# Sheet1.net
KiCad netlist of a schematic drawn in Altium Designer
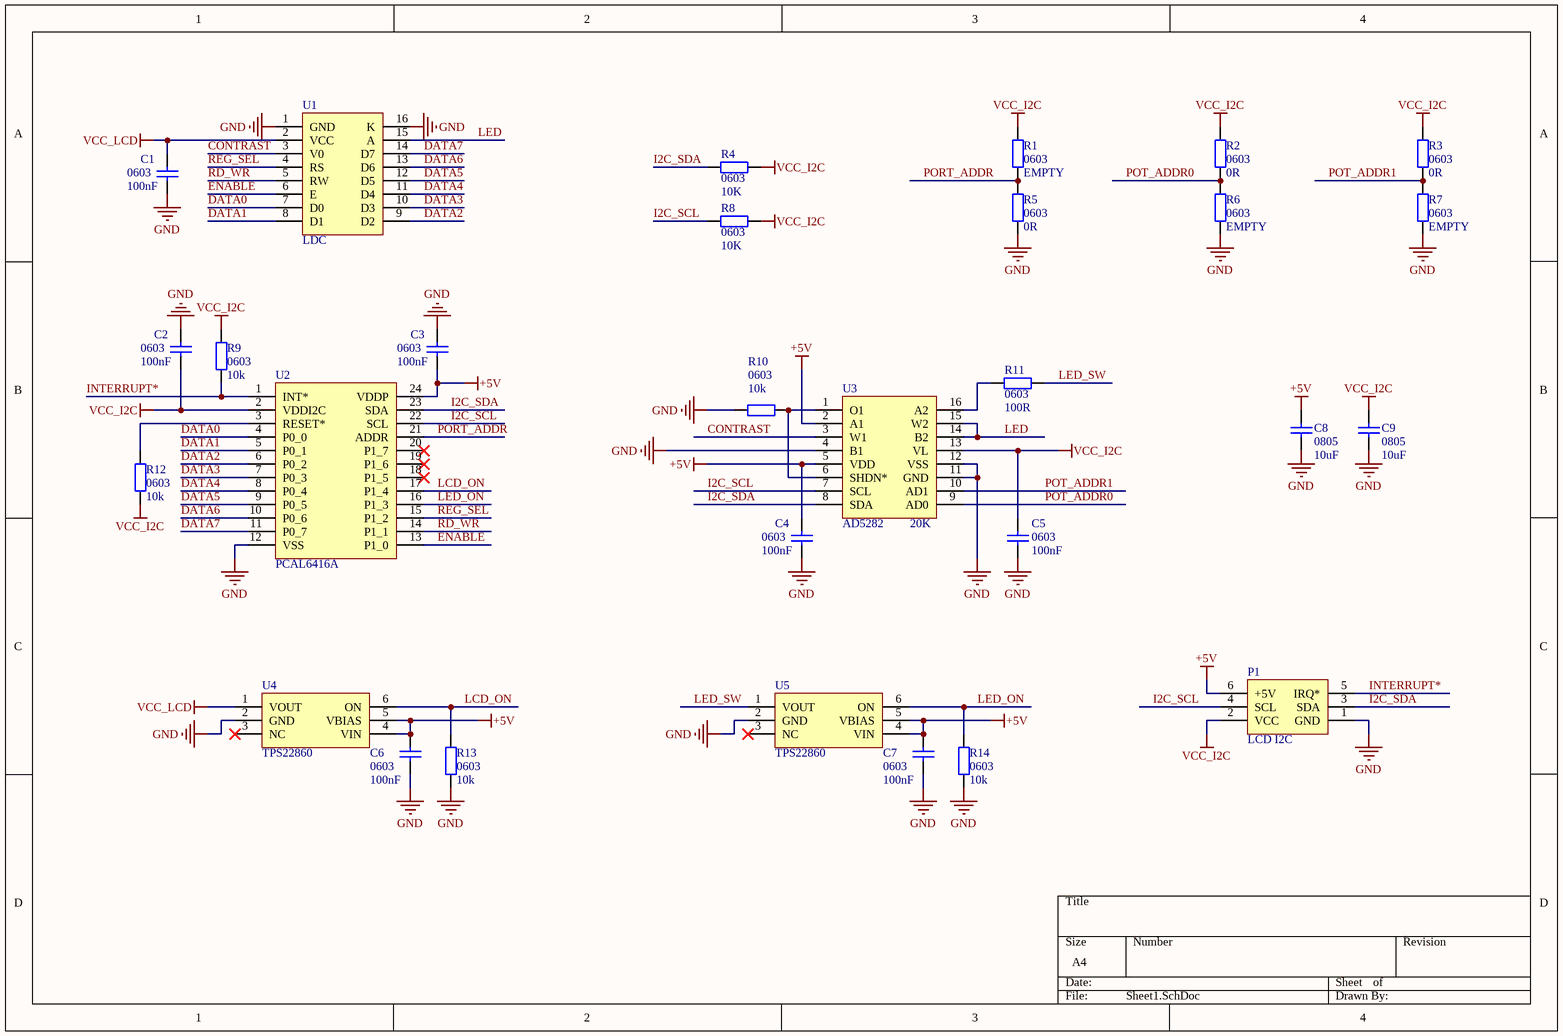
[diagram p0: Sheet1.SchDoc]

(export (version "E")
  (design (tool "Eeschema 10.0.6"))
  (components
    (comp (ref "C1")
      (value "0603")
      (footprint "0603_HandSoldering")
      (description "Capacitor")
      (fields (field (name "ALTIUM_VALUE") "100nF"))
      (libsource (lib "Schlib") (part "Capacitor"))
    )
    (comp (ref "C2")
      (value "0603")
      (footprint "0603_HandSoldering")
      (description "Capacitor")
      (fields (field (name "ALTIUM_VALUE") "100nF"))
      (libsource (lib "Schlib") (part "Capacitor"))
    )
    (comp (ref "C3")
      (value "0603")
      (footprint "0603_HandSoldering")
      (description "Capacitor")
      (fields (field (name "ALTIUM_VALUE") "100nF"))
      (libsource (lib "Schlib") (part "Capacitor"))
    )
    (comp (ref "C4")
      (value "0603")
      (footprint "0603_HandSoldering")
      (description "Capacitor")
      (fields (field (name "ALTIUM_VALUE") "100nF"))
      (libsource (lib "Schlib") (part "Capacitor"))
    )
    (comp (ref "C5")
      (value "0603")
      (footprint "0603_HandSoldering")
      (description "Capacitor")
      (fields (field (name "ALTIUM_VALUE") "100nF"))
      (libsource (lib "Schlib") (part "Capacitor"))
    )
    (comp (ref "C6")
      (value "0603")
      (footprint "0603_HandSoldering")
      (description "Capacitor")
      (fields (field (name "ALTIUM_VALUE") "100nF"))
      (libsource (lib "Schlib") (part "Capacitor"))
    )
    (comp (ref "C7")
      (value "0603")
      (footprint "0603_HandSoldering")
      (description "Capacitor")
      (fields (field (name "ALTIUM_VALUE") "100nF"))
      (libsource (lib "Schlib") (part "Capacitor"))
    )
    (comp (ref "C8")
      (value "0805")
      (footprint "0805")
      (description "Capacitor")
      (fields (field (name "ALTIUM_VALUE") "10uF"))
      (libsource (lib "Schlib") (part "Capacitor"))
    )
    (comp (ref "C9")
      (value "0805")
      (footprint "0805")
      (description "Capacitor")
      (fields (field (name "ALTIUM_VALUE") "10uF"))
      (libsource (lib "Schlib") (part "Capacitor"))
    )
    (comp (ref "P1")
      (value "LCD I2C")
      (footprint "IDC6")
      (description "LCD I2C interface")
      (libsource (lib "Schlib") (part "LCD_I2C"))
    )
    (comp (ref "R1")
      (value "0603")
      (footprint "0603_HandSoldering")
      (description "Resistor")
      (fields (field (name "ALTIUM_VALUE") "EMPTY"))
      (libsource (lib "Schlib") (part "Resistor"))
    )
    (comp (ref "R2")
      (value "0603")
      (footprint "0603_HandSoldering")
      (description "Resistor")
      (fields (field (name "ALTIUM_VALUE") "0R"))
      (libsource (lib "Schlib") (part "Resistor"))
    )
    (comp (ref "R3")
      (value "0603")
      (footprint "0603_HandSoldering")
      (description "Resistor")
      (fields (field (name "ALTIUM_VALUE") "0R"))
      (libsource (lib "Schlib") (part "Resistor"))
    )
    (comp (ref "R4")
      (value "0603")
      (footprint "0603_HandSoldering")
      (description "Resistor")
      (fields (field (name "ALTIUM_VALUE") "10K"))
      (libsource (lib "") (part "Resistor_1"))
    )
    (comp (ref "R5")
      (value "0603")
      (footprint "0603_HandSoldering")
      (description "Resistor")
      (fields (field (name "ALTIUM_VALUE") "0R"))
      (libsource (lib "Schlib") (part "Resistor"))
    )
    (comp (ref "R6")
      (value "0603")
      (footprint "0603_HandSoldering")
      (description "Resistor")
      (fields (field (name "ALTIUM_VALUE") "EMPTY"))
      (libsource (lib "Schlib") (part "Resistor"))
    )
    (comp (ref "R7")
      (value "0603")
      (footprint "0603_HandSoldering")
      (description "Resistor")
      (fields (field (name "ALTIUM_VALUE") "EMPTY"))
      (libsource (lib "Schlib") (part "Resistor"))
    )
    (comp (ref "R8")
      (value "0603")
      (footprint "0603_HandSoldering")
      (description "Resistor")
      (fields (field (name "ALTIUM_VALUE") "10K"))
      (libsource (lib "") (part "Resistor_1"))
    )
    (comp (ref "R9")
      (value "0603")
      (footprint "0603_HandSoldering")
      (description "Resistor")
      (fields (field (name "ALTIUM_VALUE") "10k"))
      (libsource (lib "") (part "Resistor_3"))
    )
    (comp (ref "R10")
      (value "0603")
      (footprint "0603_HandSoldering")
      (description "Resistor")
      (fields (field (name "ALTIUM_VALUE") "10k"))
      (libsource (lib "") (part "Resistor_1"))
    )
    (comp (ref "R11")
      (value "0603")
      (footprint "0603_HandSoldering")
      (description "Resistor")
      (fields (field (name "ALTIUM_VALUE") "100R"))
      (libsource (lib "") (part "Resistor_2"))
    )
    (comp (ref "R12")
      (value "0603")
      (footprint "0603_HandSoldering")
      (description "Resistor")
      (fields (field (name "ALTIUM_VALUE") "10k"))
      (libsource (lib "") (part "Resistor_3"))
    )
    (comp (ref "R13")
      (value "0603")
      (footprint "0603_HandSoldering")
      (description "Resistor")
      (fields (field (name "ALTIUM_VALUE") "10k"))
      (libsource (lib "Schlib") (part "Resistor"))
    )
    (comp (ref "R14")
      (value "0603")
      (footprint "0603_HandSoldering")
      (description "Resistor")
      (fields (field (name "ALTIUM_VALUE") "10k"))
      (libsource (lib "Schlib") (part "Resistor"))
    )
    (comp (ref "U1")
      (value "LDC")
      (footprint "LCD_2x16_Board")
      (description "2x16 LCD PCB")
      (libsource (lib "Schlib") (part "LCD_2x16_Board"))
    )
    (comp (ref "U2")
      (value "PCAL6416A")
      (footprint "PCAL6416A_TSOP24")
      (description "I2C to parallel converter")
      (libsource (lib "Schlib") (part "PCAL6416A"))
    )
    (comp (ref "U3")
      (value "AD5282")
      (footprint "AD5282_TSSOP16")
      (description "Dual digital potentiometer")
      (fields (field (name "ALTIUM_VALUE") "20K"))
      (libsource (lib "Schlib") (part "AD5282"))
    )
    (comp (ref "U4")
      (value "TPS22860")
      (footprint "TPS22860_SOT23_6")
      (description "Power switch")
      (libsource (lib "Schlib") (part "TPS22860"))
    )
    (comp (ref "U5")
      (value "TPS22860")
      (footprint "TPS22860_SOT23_6")
      (description "Power switch")
      (libsource (lib "Schlib") (part "TPS22860"))
    )
  )
  (nets
    (net (code "1") (name "+5V") (class "Default")
      (node (ref "C3") (pin "1") (pinfunction "1_1") (pintype "passive"))
      (node (ref "C4") (pin "2") (pinfunction "2_2") (pintype "passive"))
      (node (ref "C6") (pin "1") (pinfunction "1_1") (pintype "passive"))
      (node (ref "C7") (pin "1") (pinfunction "1_1") (pintype "passive"))
      (node (ref "C8") (pin "2") (pinfunction "2_2") (pintype "passive"))
      (node (ref "P1") (pin "6") (pinfunction "+5V_6") (pintype "passive"))
      (node (ref "U2") (pin "24") (pinfunction "VDDP_24") (pintype "passive"))
      (node (ref "U3") (pin "2") (pinfunction "A1_2") (pintype "passive"))
      (node (ref "U3") (pin "5") (pinfunction "VDD_5") (pintype "passive"))
      (node (ref "U4") (pin "4") (pinfunction "VIN_4") (pintype "passive"))
      (node (ref "U4") (pin "5") (pinfunction "VBIAS_5") (pintype "passive"))
      (node (ref "U5") (pin "4") (pinfunction "VIN_4") (pintype "passive"))
      (node (ref "U5") (pin "5") (pinfunction "VBIAS_5") (pintype "passive"))
    )
    (net (code "2") (name "/CONTRAST") (class "Default")
      (node (ref "U1") (pin "3") (pinfunction "V0_3") (pintype "passive"))
      (node (ref "U3") (pin "3") (pinfunction "W1_3") (pintype "passive"))
    )
    (net (code "3") (name "/DATA0") (class "Default")
      (node (ref "U1") (pin "7") (pinfunction "D0_7") (pintype "passive"))
      (node (ref "U2") (pin "4") (pinfunction "P0_0_4") (pintype "passive"))
    )
    (net (code "4") (name "/DATA1") (class "Default")
      (node (ref "U1") (pin "8") (pinfunction "D1_8") (pintype "passive"))
      (node (ref "U2") (pin "5") (pinfunction "P0_1_5") (pintype "passive"))
    )
    (net (code "5") (name "/DATA2") (class "Default")
      (node (ref "U1") (pin "9") (pinfunction "D2_9") (pintype "passive"))
      (node (ref "U2") (pin "6") (pinfunction "P0_2_6") (pintype "passive"))
    )
    (net (code "6") (name "/DATA3") (class "Default")
      (node (ref "U1") (pin "10") (pinfunction "D3_10") (pintype "passive"))
      (node (ref "U2") (pin "7") (pinfunction "P0_3_7") (pintype "passive"))
    )
    (net (code "7") (name "/DATA4") (class "Default")
      (node (ref "U1") (pin "11") (pinfunction "D4_11") (pintype "passive"))
      (node (ref "U2") (pin "8") (pinfunction "P0_4_8") (pintype "passive"))
    )
    (net (code "8") (name "/DATA5") (class "Default")
      (node (ref "U1") (pin "12") (pinfunction "D5_12") (pintype "passive"))
      (node (ref "U2") (pin "9") (pinfunction "P0_5_9") (pintype "passive"))
    )
    (net (code "9") (name "/DATA6") (class "Default")
      (node (ref "U1") (pin "13") (pinfunction "D6_13") (pintype "passive"))
      (node (ref "U2") (pin "10") (pinfunction "P0_6_10") (pintype "passive"))
    )
    (net (code "10") (name "/DATA7") (class "Default")
      (node (ref "U1") (pin "14") (pinfunction "D7_14") (pintype "passive"))
      (node (ref "U2") (pin "11") (pinfunction "P0_7_11") (pintype "passive"))
    )
    (net (code "11") (name "/ENABLE") (class "Default")
      (node (ref "U1") (pin "6") (pinfunction "E_6") (pintype "passive"))
      (node (ref "U2") (pin "13") (pinfunction "P1_0_13") (pintype "passive"))
    )
    (net (code "12") (name "/I2C_SCL") (class "Default")
      (node (ref "P1") (pin "4") (pinfunction "SCL_4") (pintype "passive"))
      (node (ref "R8") (pin "1") (pinfunction "1_1") (pintype "passive"))
      (node (ref "U2") (pin "22") (pinfunction "SCL_22") (pintype "passive"))
      (node (ref "U3") (pin "7") (pinfunction "SCL_7") (pintype "passive"))
    )
    (net (code "13") (name "/I2C_SDA") (class "Default")
      (node (ref "P1") (pin "3") (pinfunction "SDA_3") (pintype "passive"))
      (node (ref "R4") (pin "1") (pinfunction "1_1") (pintype "passive"))
      (node (ref "U2") (pin "23") (pinfunction "SDA_23") (pintype "passive"))
      (node (ref "U3") (pin "8") (pinfunction "SDA_8") (pintype "passive"))
    )
    (net (code "14") (name "/INTERRUPT*") (class "Default")
      (node (ref "P1") (pin "5") (pinfunction "IRQ*_5") (pintype "passive"))
      (node (ref "R9") (pin "2") (pinfunction "2_2") (pintype "passive"))
      (node (ref "U2") (pin "1") (pinfunction "INT*_1") (pintype "passive"))
    )
    (net (code "15") (name "/LCD_ON") (class "Default")
      (node (ref "R13") (pin "2") (pinfunction "2_2") (pintype "passive"))
      (node (ref "U2") (pin "17") (pinfunction "P1_4_17") (pintype "passive"))
      (node (ref "U4") (pin "6") (pinfunction "ON_6") (pintype "passive"))
    )
    (net (code "16") (name "/LED") (class "Default")
      (node (ref "U1") (pin "15") (pinfunction "A_15") (pintype "passive"))
      (node (ref "U3") (pin "14") (pinfunction "B2_14") (pintype "passive"))
      (node (ref "U3") (pin "15") (pinfunction "W2_15") (pintype "passive"))
    )
    (net (code "17") (name "/LED_ON") (class "Default")
      (node (ref "R14") (pin "2") (pinfunction "2_2") (pintype "passive"))
      (node (ref "U2") (pin "16") (pinfunction "P1_3_16") (pintype "passive"))
      (node (ref "U5") (pin "6") (pinfunction "ON_6") (pintype "passive"))
    )
    (net (code "18") (name "/LED_SW") (class "Default")
      (node (ref "R11") (pin "1") (pinfunction "1_1") (pintype "passive"))
      (node (ref "U5") (pin "1") (pinfunction "VOUT_1") (pintype "passive"))
    )
    (net (code "19") (name "/PORT_ADDR") (class "Default")
      (node (ref "R1") (pin "1") (pinfunction "1_1") (pintype "passive"))
      (node (ref "R5") (pin "2") (pinfunction "2_2") (pintype "passive"))
      (node (ref "U2") (pin "21") (pinfunction "ADDR_21") (pintype "passive"))
    )
    (net (code "20") (name "/POT_ADDR0") (class "Default")
      (node (ref "R2") (pin "1") (pinfunction "1_1") (pintype "passive"))
      (node (ref "R6") (pin "2") (pinfunction "2_2") (pintype "passive"))
      (node (ref "U3") (pin "9") (pinfunction "AD0_9") (pintype "passive"))
    )
    (net (code "21") (name "/POT_ADDR1") (class "Default")
      (node (ref "R3") (pin "1") (pinfunction "1_1") (pintype "passive"))
      (node (ref "R7") (pin "2") (pinfunction "2_2") (pintype "passive"))
      (node (ref "U3") (pin "10") (pinfunction "AD1_10") (pintype "passive"))
    )
    (net (code "22") (name "/RD_WR") (class "Default")
      (node (ref "U1") (pin "5") (pinfunction "RW_5") (pintype "passive"))
      (node (ref "U2") (pin "14") (pinfunction "P1_1_14") (pintype "passive"))
    )
    (net (code "23") (name "/REG_SEL") (class "Default")
      (node (ref "U1") (pin "4") (pinfunction "RS_4") (pintype "passive"))
      (node (ref "U2") (pin "15") (pinfunction "P1_2_15") (pintype "passive"))
    )
    (net (code "24") (name "GND") (class "Default")
      (node (ref "C1") (pin "1") (pinfunction "1_1") (pintype "passive"))
      (node (ref "C2") (pin "2") (pinfunction "2_2") (pintype "passive"))
      (node (ref "C3") (pin "2") (pinfunction "2_2") (pintype "passive"))
      (node (ref "C4") (pin "1") (pinfunction "1_1") (pintype "passive"))
      (node (ref "C5") (pin "2") (pinfunction "2_2") (pintype "passive"))
      (node (ref "C6") (pin "2") (pinfunction "2_2") (pintype "passive"))
      (node (ref "C7") (pin "2") (pinfunction "2_2") (pintype "passive"))
      (node (ref "C8") (pin "1") (pinfunction "1_1") (pintype "passive"))
      (node (ref "C9") (pin "1") (pinfunction "1_1") (pintype "passive"))
      (node (ref "P1") (pin "1") (pinfunction "GND_1") (pintype "passive"))
      (node (ref "R10") (pin "1") (pinfunction "1_1") (pintype "passive"))
      (node (ref "R13") (pin "1") (pinfunction "1_1") (pintype "passive"))
      (node (ref "R14") (pin "1") (pinfunction "1_1") (pintype "passive"))
      (node (ref "R5") (pin "1") (pinfunction "1_1") (pintype "passive"))
      (node (ref "R6") (pin "1") (pinfunction "1_1") (pintype "passive"))
      (node (ref "R7") (pin "1") (pinfunction "1_1") (pintype "passive"))
      (node (ref "U1") (pin "1") (pinfunction "GND_1") (pintype "passive"))
      (node (ref "U1") (pin "16") (pinfunction "K_16") (pintype "passive"))
      (node (ref "U2") (pin "12") (pinfunction "VSS_12") (pintype "passive"))
      (node (ref "U3") (pin "11") (pinfunction "GND_11") (pintype "passive"))
      (node (ref "U3") (pin "12") (pinfunction "VSS_12") (pintype "passive"))
      (node (ref "U3") (pin "4") (pinfunction "B1_4") (pintype "passive"))
      (node (ref "U4") (pin "2") (pinfunction "GND_2") (pintype "passive"))
      (node (ref "U5") (pin "2") (pinfunction "GND_2") (pintype "passive"))
    )
    (net (code "25") (name "Net-(U2-RESET*)") (class "Default")
      (node (ref "R12") (pin "1") (pinfunction "1_1") (pintype "passive"))
      (node (ref "U2") (pin "3") (pinfunction "RESET*_3") (pintype "passive"))
    )
    (net (code "26") (name "Net-(U3-A2)") (class "Default")
      (node (ref "R11") (pin "2") (pinfunction "2_2") (pintype "passive"))
      (node (ref "U3") (pin "16") (pinfunction "A2_16") (pintype "passive"))
    )
    (net (code "27") (name "Net-(U3-O1)") (class "Default")
      (node (ref "R10") (pin "2") (pinfunction "2_2") (pintype "passive"))
      (node (ref "U3") (pin "1") (pinfunction "O1_1") (pintype "passive"))
      (node (ref "U3") (pin "6") (pinfunction "SHDN*_6") (pintype "passive"))
    )
    (net (code "28") (name "VCC_I2C") (class "Default")
      (node (ref "C2") (pin "1") (pinfunction "1_1") (pintype "passive"))
      (node (ref "C5") (pin "1") (pinfunction "1_1") (pintype "passive"))
      (node (ref "C9") (pin "2") (pinfunction "2_2") (pintype "passive"))
      (node (ref "P1") (pin "2") (pinfunction "VCC_2") (pintype "passive"))
      (node (ref "R1") (pin "2") (pinfunction "2_2") (pintype "passive"))
      (node (ref "R12") (pin "2") (pinfunction "2_2") (pintype "passive"))
      (node (ref "R2") (pin "2") (pinfunction "2_2") (pintype "passive"))
      (node (ref "R3") (pin "2") (pinfunction "2_2") (pintype "passive"))
      (node (ref "R4") (pin "2") (pinfunction "2_2") (pintype "passive"))
      (node (ref "R8") (pin "2") (pinfunction "2_2") (pintype "passive"))
      (node (ref "R9") (pin "1") (pinfunction "1_1") (pintype "passive"))
      (node (ref "U2") (pin "2") (pinfunction "VDDI2C_2") (pintype "passive"))
      (node (ref "U3") (pin "13") (pinfunction "VL_13") (pintype "passive"))
    )
    (net (code "29") (name "VCC_LCD") (class "Default")
      (node (ref "C1") (pin "2") (pinfunction "2_2") (pintype "passive"))
      (node (ref "U1") (pin "2") (pinfunction "VCC_2") (pintype "passive"))
      (node (ref "U4") (pin "1") (pinfunction "VOUT_1") (pintype "passive"))
    )
    (net (code "30") (name "unconnected-(U2-P1_5-Pad18)") (class "Default")
      (node (ref "U2") (pin "18") (pinfunction "P1_5_18") (pintype "passive+no_connect"))
    )
    (net (code "31") (name "unconnected-(U2-P1_6-Pad19)") (class "Default")
      (node (ref "U2") (pin "19") (pinfunction "P1_6_19") (pintype "passive+no_connect"))
    )
    (net (code "32") (name "unconnected-(U2-P1_7-Pad20)") (class "Default")
      (node (ref "U2") (pin "20") (pinfunction "P1_7_20") (pintype "passive+no_connect"))
    )
    (net (code "33") (name "unconnected-(U4-NC-Pad3)") (class "Default")
      (node (ref "U4") (pin "3") (pinfunction "NC_3") (pintype "passive+no_connect"))
    )
    (net (code "34") (name "unconnected-(U5-NC-Pad3)") (class "Default")
      (node (ref "U5") (pin "3") (pinfunction "NC_3") (pintype "passive+no_connect"))
    )
  )
)
